# Two_Nine_Five_Rev_2.net
KiCad netlist of a schematic drawn in EAGLE
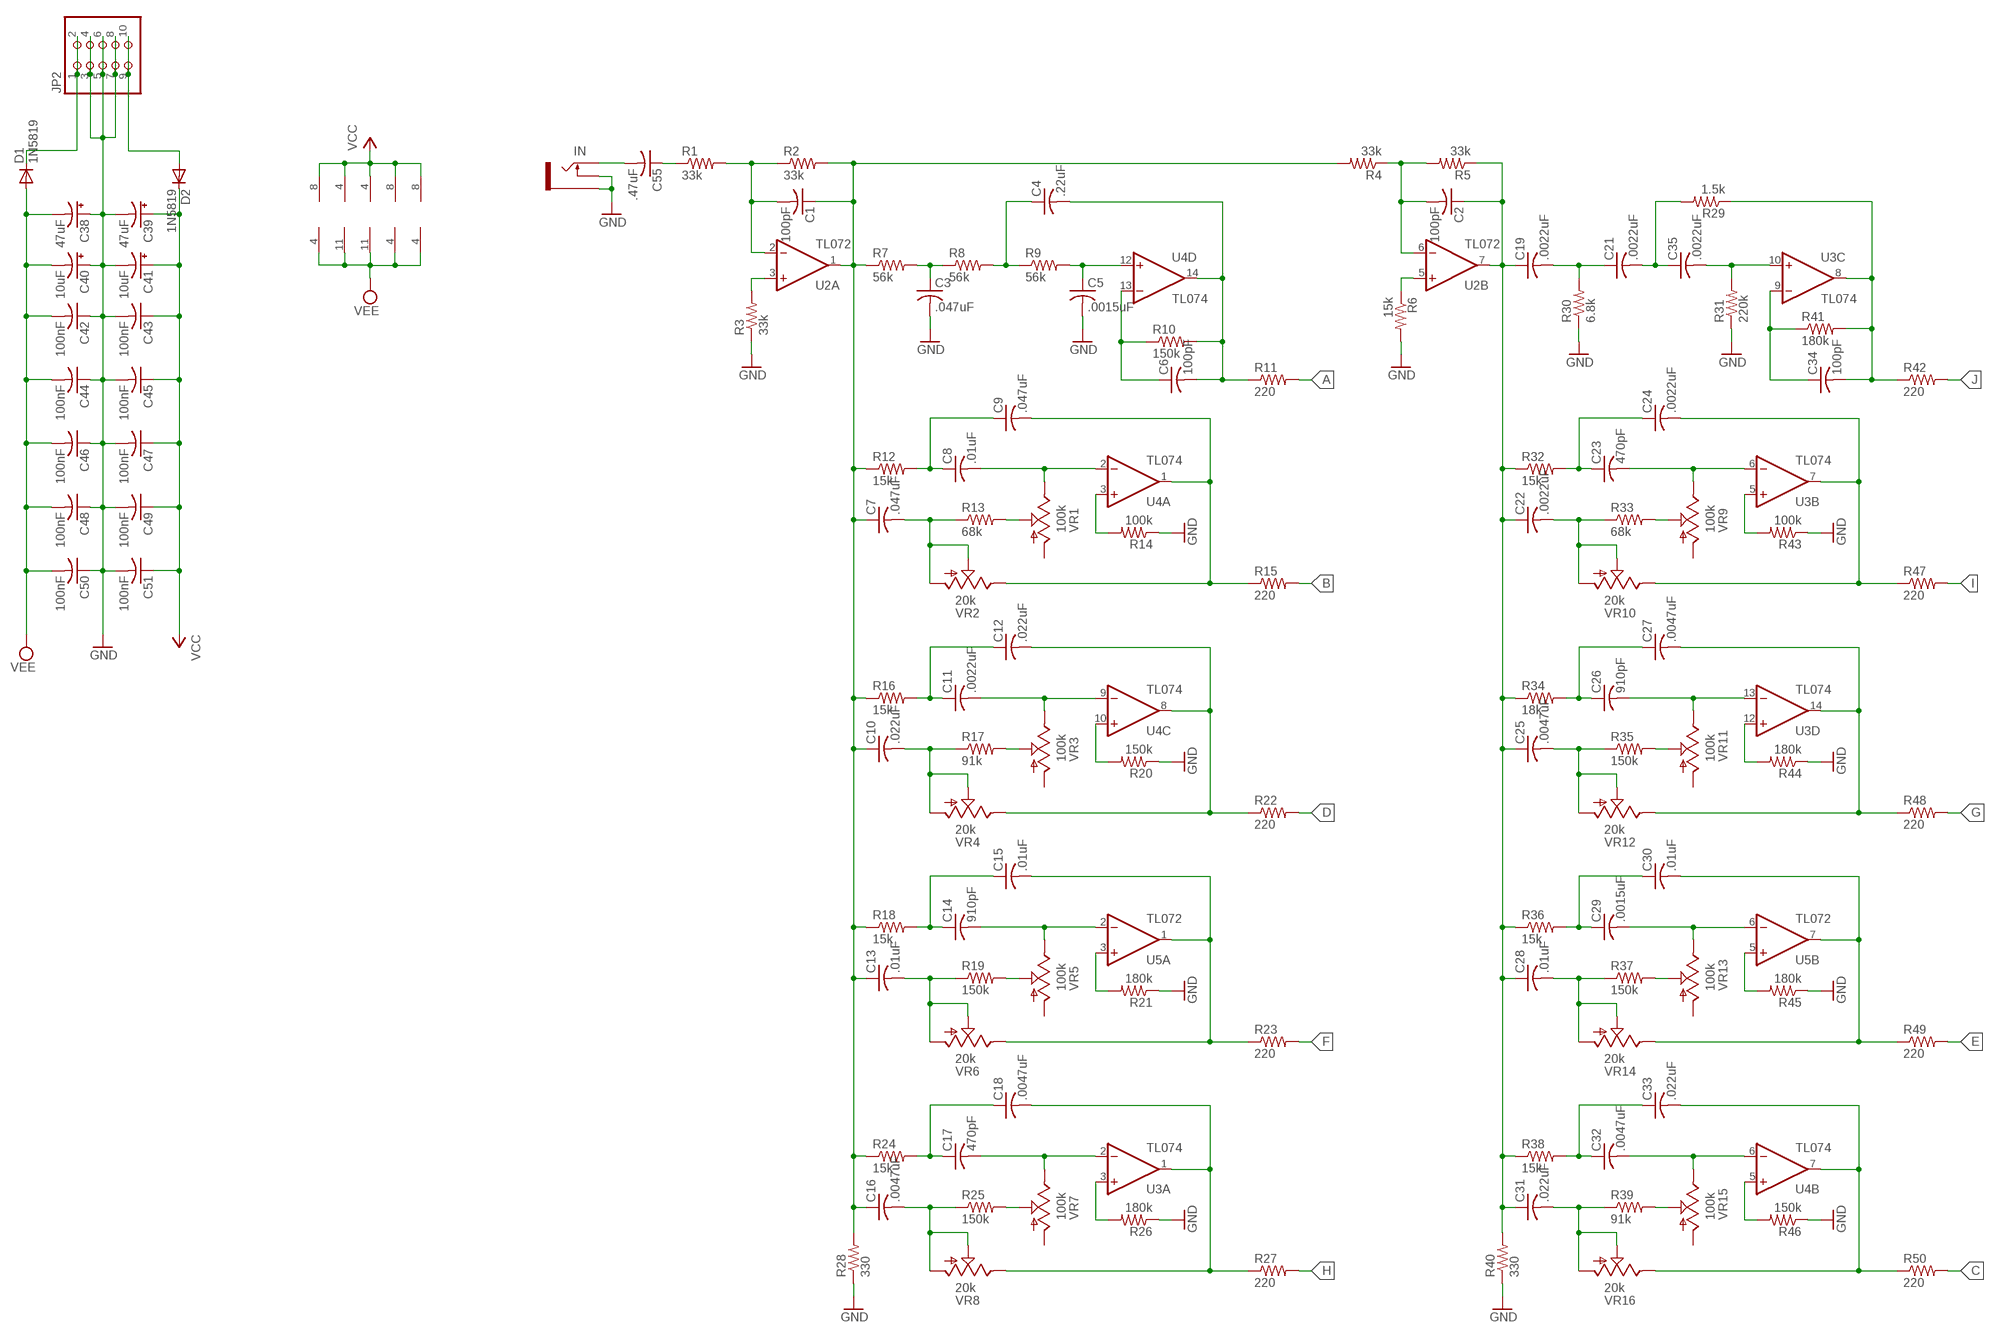
[diagram p0: schematic, sheet 1, part 1 of 2]
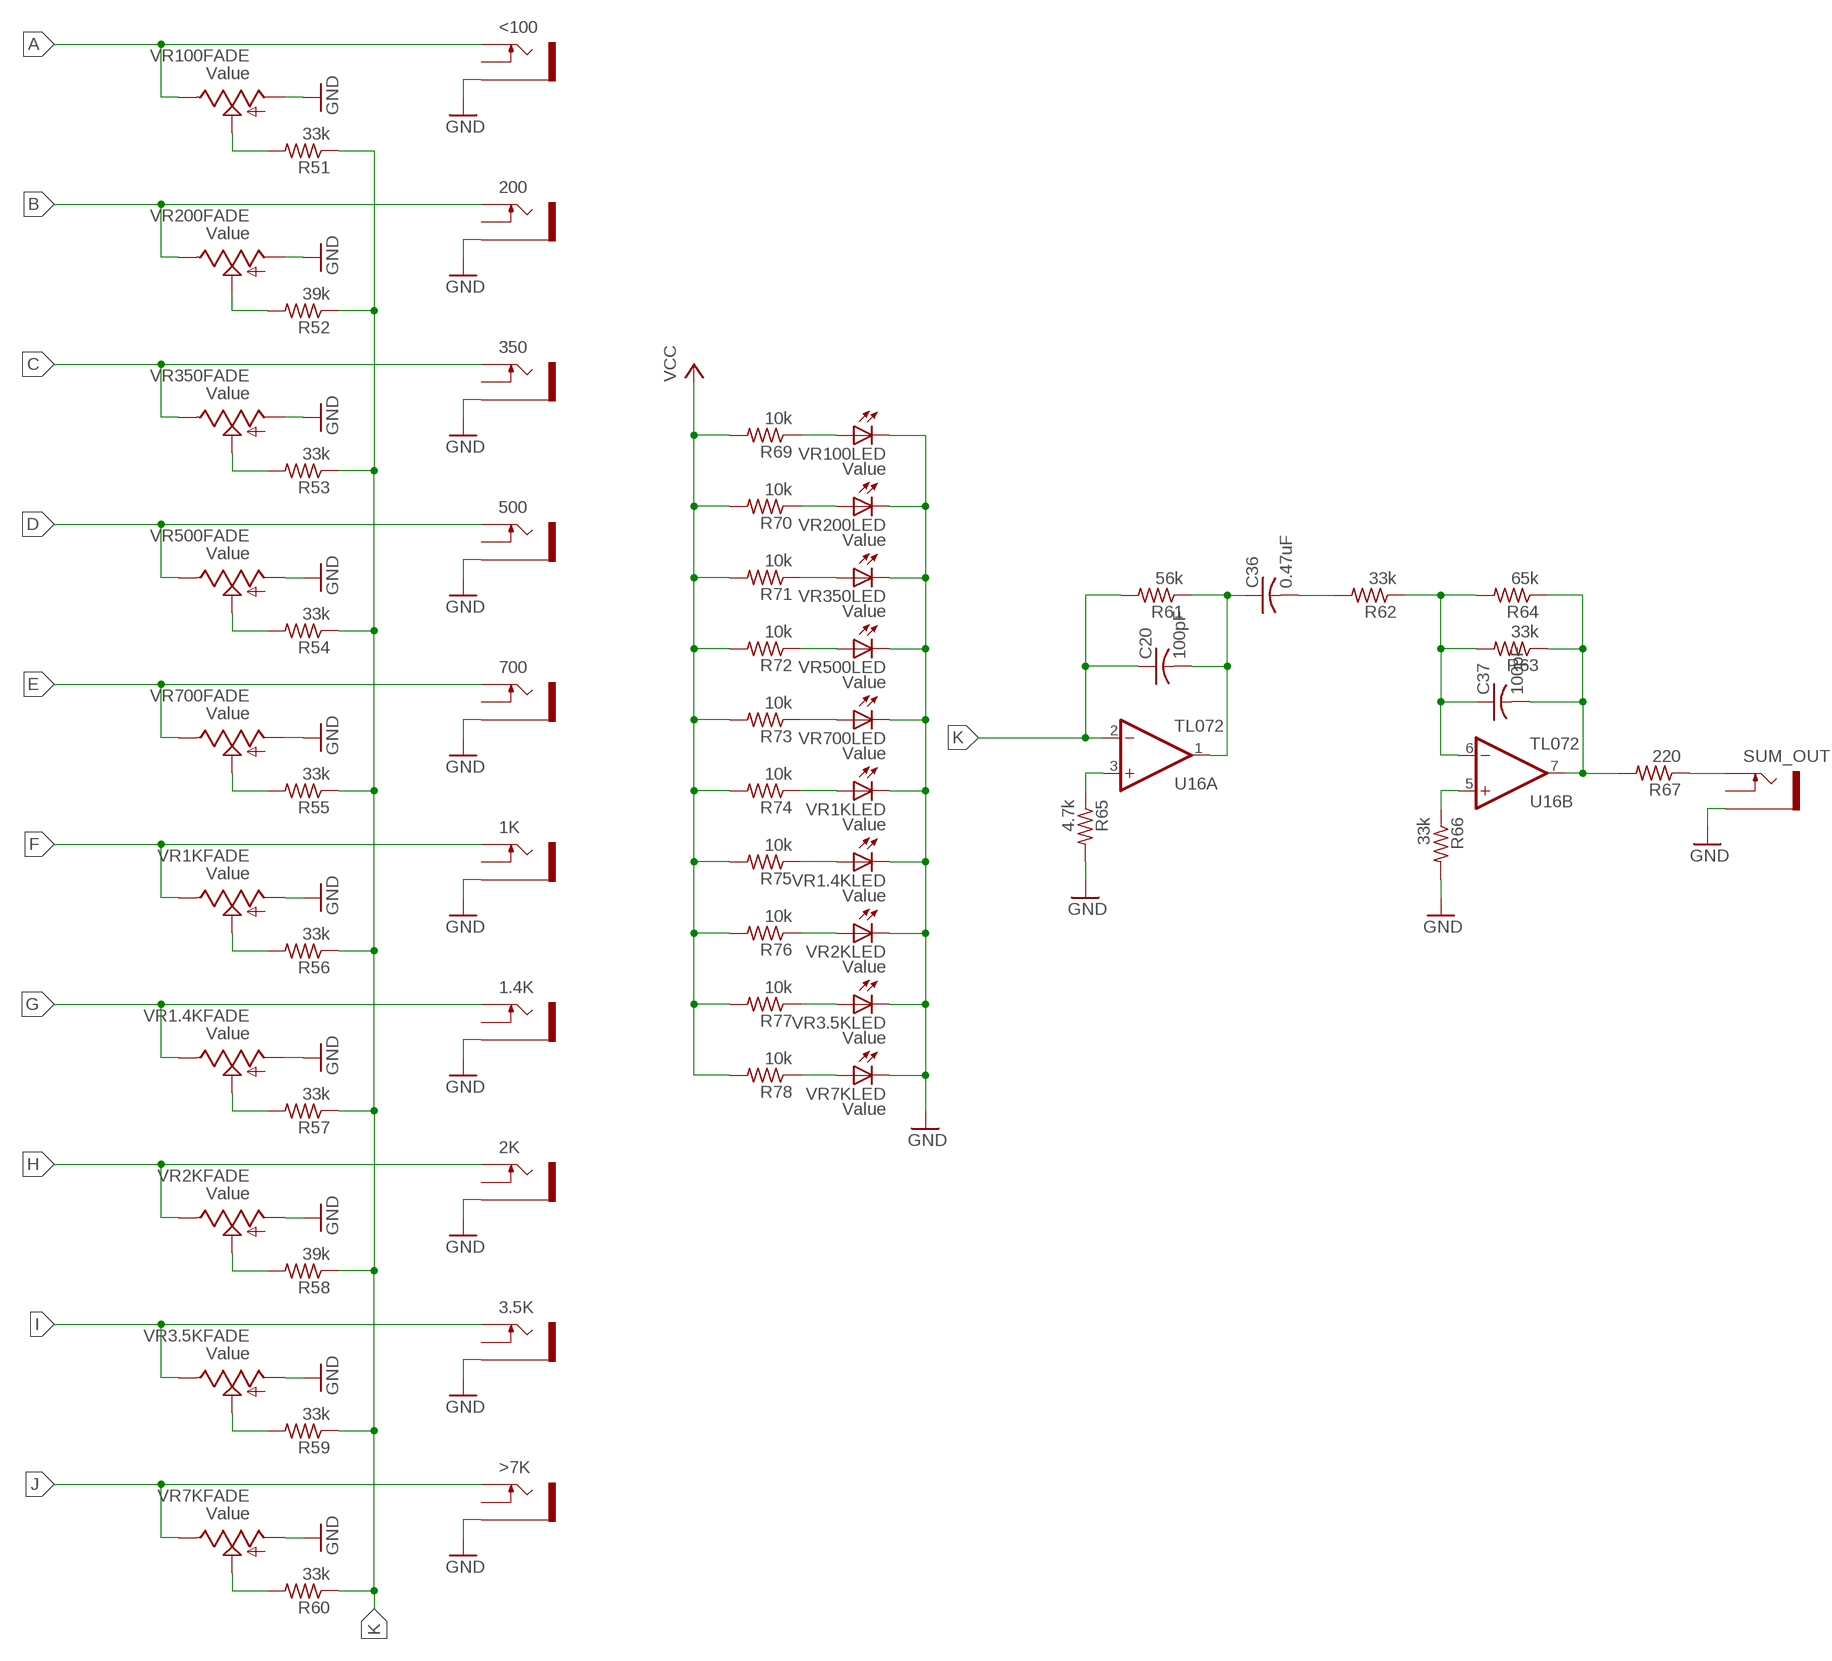
[diagram p1: schematic, sheet 1, part 2 of 2]

(export (version "E")
  (design (tool "Eeschema 10.0.6"))
  (components
    (comp (ref "1.4K")
      (value "THONKICONNNEW")
      (footprint "eagle-import:WQP-PJ301M-12_JACK")
      (libsource (lib "eagle-import") (part "THONKICONNNEW"))
    )
    (comp (ref "1K")
      (value "THONKICONNNEW")
      (footprint "eagle-import:WQP-PJ301M-12_JACK")
      (libsource (lib "eagle-import") (part "THONKICONNNEW"))
    )
    (comp (ref "2K")
      (value "THONKICONNNEW")
      (footprint "eagle-import:WQP-PJ301M-12_JACK")
      (libsource (lib "eagle-import") (part "THONKICONNNEW"))
    )
    (comp (ref "3.5K")
      (value "THONKICONNNEW")
      (footprint "eagle-import:WQP-PJ301M-12_JACK")
      (libsource (lib "eagle-import") (part "THONKICONNNEW"))
    )
    (comp (ref "200")
      (value "THONKICONNNEW")
      (footprint "eagle-import:WQP-PJ301M-12_JACK")
      (libsource (lib "eagle-import") (part "THONKICONNNEW"))
    )
    (comp (ref "350")
      (value "THONKICONNNEW")
      (footprint "eagle-import:WQP-PJ301M-12_JACK")
      (libsource (lib "eagle-import") (part "THONKICONNNEW"))
    )
    (comp (ref "500")
      (value "THONKICONNNEW")
      (footprint "eagle-import:WQP-PJ301M-12_JACK")
      (libsource (lib "eagle-import") (part "THONKICONNNEW"))
    )
    (comp (ref "700")
      (value "THONKICONNNEW")
      (footprint "eagle-import:WQP-PJ301M-12_JACK")
      (libsource (lib "eagle-import") (part "THONKICONNNEW"))
    )
    (comp (ref "<100")
      (value "THONKICONNNEW")
      (footprint "eagle-import:WQP-PJ301M-12_JACK")
      (libsource (lib "eagle-import") (part "THONKICONNNEW"))
    )
    (comp (ref ">7K")
      (value "THONKICONNNEW")
      (footprint "eagle-import:WQP-PJ301M-12_JACK")
      (libsource (lib "eagle-import") (part "THONKICONNNEW"))
    )
    (comp (ref "C1")
      (value "100pF")
      (footprint "eagle-import:C0603")
      (libsource (lib "eagle-import") (part "C-USC0603"))
    )
    (comp (ref "C2")
      (value "100pF")
      (footprint "eagle-import:C0603")
      (libsource (lib "eagle-import") (part "C-USC0603"))
    )
    (comp (ref "C3")
      (value ".047uF")
      (footprint "eagle-import:C0603")
      (libsource (lib "eagle-import") (part "C-USC0603"))
    )
    (comp (ref "C4")
      (value ".22uF")
      (footprint "eagle-import:C0603")
      (libsource (lib "eagle-import") (part "C-USC0603"))
    )
    (comp (ref "C5")
      (value ".0015uF")
      (footprint "eagle-import:C0603")
      (libsource (lib "eagle-import") (part "C-USC0603"))
    )
    (comp (ref "C6")
      (value "100pF")
      (footprint "eagle-import:C0603")
      (libsource (lib "eagle-import") (part "C-USC0603"))
    )
    (comp (ref "C7")
      (value ".047uF")
      (footprint "eagle-import:C0603")
      (libsource (lib "eagle-import") (part "C-USC0603"))
    )
    (comp (ref "C8")
      (value ".01uF")
      (footprint "eagle-import:C0603")
      (libsource (lib "eagle-import") (part "C-USC0603"))
    )
    (comp (ref "C9")
      (value ".047uF")
      (footprint "eagle-import:C0603")
      (libsource (lib "eagle-import") (part "C-USC0603"))
    )
    (comp (ref "C10")
      (value ".022uF")
      (footprint "eagle-import:C0603")
      (libsource (lib "eagle-import") (part "C-USC0603"))
    )
    (comp (ref "C11")
      (value ".0022uF")
      (footprint "eagle-import:C0603")
      (libsource (lib "eagle-import") (part "C-USC0603"))
    )
    (comp (ref "C12")
      (value ".022uF")
      (footprint "eagle-import:C0603")
      (libsource (lib "eagle-import") (part "C-USC0603"))
    )
    (comp (ref "C13")
      (value ".01uF")
      (footprint "eagle-import:C0603")
      (libsource (lib "eagle-import") (part "C-USC0603"))
    )
    (comp (ref "C14")
      (value "910pF")
      (footprint "eagle-import:C0603")
      (libsource (lib "eagle-import") (part "C-USC0603"))
    )
    (comp (ref "C15")
      (value ".01uF")
      (footprint "eagle-import:C0603")
      (libsource (lib "eagle-import") (part "C-USC0603"))
    )
    (comp (ref "C16")
      (value ".0047uF")
      (footprint "eagle-import:C0603")
      (libsource (lib "eagle-import") (part "C-USC0603"))
    )
    (comp (ref "C17")
      (value "470pF")
      (footprint "eagle-import:C0603")
      (libsource (lib "eagle-import") (part "C-USC0603"))
    )
    (comp (ref "C18")
      (value ".0047uF")
      (footprint "eagle-import:C0603")
      (libsource (lib "eagle-import") (part "C-USC0603"))
    )
    (comp (ref "C19")
      (value ".0022uF")
      (footprint "eagle-import:C0603")
      (libsource (lib "eagle-import") (part "C-USC0603"))
    )
    (comp (ref "C20")
      (value "100pF")
      (footprint "eagle-import:C0603")
      (libsource (lib "eagle-import") (part "C-USC0603"))
    )
    (comp (ref "C21")
      (value ".0022uF")
      (footprint "eagle-import:C0603")
      (libsource (lib "eagle-import") (part "C-USC0603"))
    )
    (comp (ref "C22")
      (value ".0022uF")
      (footprint "eagle-import:C0603")
      (libsource (lib "eagle-import") (part "C-USC0603"))
    )
    (comp (ref "C23")
      (value "470pF")
      (footprint "eagle-import:C0603")
      (libsource (lib "eagle-import") (part "C-USC0603"))
    )
    (comp (ref "C24")
      (value ".0022uF")
      (footprint "eagle-import:C0603")
      (libsource (lib "eagle-import") (part "C-USC0603"))
    )
    (comp (ref "C25")
      (value ".0047uF")
      (footprint "eagle-import:C0603")
      (libsource (lib "eagle-import") (part "C-USC0603"))
    )
    (comp (ref "C26")
      (value "910pF")
      (footprint "eagle-import:C0603")
      (libsource (lib "eagle-import") (part "C-USC0603"))
    )
    (comp (ref "C27")
      (value ".0047uF")
      (footprint "eagle-import:C0603")
      (libsource (lib "eagle-import") (part "C-USC0603"))
    )
    (comp (ref "C28")
      (value ".01uF")
      (footprint "eagle-import:C0603")
      (libsource (lib "eagle-import") (part "C-USC0603"))
    )
    (comp (ref "C29")
      (value ".0015uF")
      (footprint "eagle-import:C0603")
      (libsource (lib "eagle-import") (part "C-USC0603"))
    )
    (comp (ref "C30")
      (value ".01uF")
      (footprint "eagle-import:C0603")
      (libsource (lib "eagle-import") (part "C-USC0603"))
    )
    (comp (ref "C31")
      (value ".022uF")
      (footprint "eagle-import:C0603")
      (libsource (lib "eagle-import") (part "C-USC0603"))
    )
    (comp (ref "C32")
      (value ".0047uF")
      (footprint "eagle-import:C0603")
      (libsource (lib "eagle-import") (part "C-USC0603"))
    )
    (comp (ref "C33")
      (value ".022uF")
      (footprint "eagle-import:C0603")
      (libsource (lib "eagle-import") (part "C-USC0603"))
    )
    (comp (ref "C34")
      (value "100pF")
      (footprint "eagle-import:C0603")
      (libsource (lib "eagle-import") (part "C-USC0603"))
    )
    (comp (ref "C35")
      (value ".0022uF")
      (footprint "eagle-import:C0603")
      (libsource (lib "eagle-import") (part "C-USC0603"))
    )
    (comp (ref "C36")
      (value "0.47uF")
      (footprint "eagle-import:C0603")
      (libsource (lib "eagle-import") (part "C-USC0603"))
    )
    (comp (ref "C37")
      (value "100pF")
      (footprint "eagle-import:C0603")
      (libsource (lib "eagle-import") (part "C-USC0603"))
    )
    (comp (ref "C38")
      (value "47uF")
      (footprint "eagle-import:PANASONIC_D")
      (libsource (lib "eagle-import") (part "CPOL-USD"))
    )
    (comp (ref "C39")
      (value "47uF")
      (footprint "eagle-import:PANASONIC_D")
      (libsource (lib "eagle-import") (part "CPOL-USD"))
    )
    (comp (ref "C40")
      (value "10uF")
      (footprint "eagle-import:PANASONIC_B")
      (libsource (lib "eagle-import") (part "CPOL-USB"))
    )
    (comp (ref "C41")
      (value "10uF")
      (footprint "eagle-import:PANASONIC_B")
      (libsource (lib "eagle-import") (part "CPOL-USB"))
    )
    (comp (ref "C42")
      (value "100nF")
      (footprint "eagle-import:C0603")
      (libsource (lib "eagle-import") (part "C-USC0603"))
    )
    (comp (ref "C43")
      (value "100nF")
      (footprint "eagle-import:C0603")
      (libsource (lib "eagle-import") (part "C-USC0603"))
    )
    (comp (ref "C44")
      (value "100nF")
      (footprint "eagle-import:C0603")
      (libsource (lib "eagle-import") (part "C-USC0603"))
    )
    (comp (ref "C45")
      (value "100nF")
      (footprint "eagle-import:C0603")
      (libsource (lib "eagle-import") (part "C-USC0603"))
    )
    (comp (ref "C46")
      (value "100nF")
      (footprint "eagle-import:C0603")
      (libsource (lib "eagle-import") (part "C-USC0603"))
    )
    (comp (ref "C47")
      (value "100nF")
      (footprint "eagle-import:C0603")
      (libsource (lib "eagle-import") (part "C-USC0603"))
    )
    (comp (ref "C48")
      (value "100nF")
      (footprint "eagle-import:C0603")
      (libsource (lib "eagle-import") (part "C-USC0603"))
    )
    (comp (ref "C49")
      (value "100nF")
      (footprint "eagle-import:C0603")
      (libsource (lib "eagle-import") (part "C-USC0603"))
    )
    (comp (ref "C50")
      (value "100nF")
      (footprint "eagle-import:C0603")
      (libsource (lib "eagle-import") (part "C-USC0603"))
    )
    (comp (ref "C51")
      (value "100nF")
      (footprint "eagle-import:C0603")
      (libsource (lib "eagle-import") (part "C-USC0603"))
    )
    (comp (ref "C55")
      (value ".47uF")
      (footprint "eagle-import:C0603")
      (libsource (lib "eagle-import") (part "C-USC0603"))
    )
    (comp (ref "D1")
      (value "1N5819")
      (footprint "eagle-import:SOD123")
      (libsource (lib "eagle-import") (part "DIODE-SOD123"))
    )
    (comp (ref "D2")
      (value "1N5819")
      (footprint "eagle-import:SOD123")
      (libsource (lib "eagle-import") (part "DIODE-SOD123"))
    )
    (comp (ref "IN")
      (value "THONKICONNNEW")
      (footprint "eagle-import:WQP-PJ301M-12_JACK")
      (libsource (lib "eagle-import") (part "THONKICONNNEW"))
    )
    (comp (ref "JP2")
      (value "PINHD-2X5SMT")
      (footprint "eagle-import:2X05_SMT")
      (libsource (lib "eagle-import") (part "PINHD-2X5SMT"))
    )
    (comp (ref "R1")
      (value "33k")
      (footprint "eagle-import:R0603")
      (libsource (lib "eagle-import") (part "R-US_R0603"))
    )
    (comp (ref "R2")
      (value "33k")
      (footprint "eagle-import:R0603")
      (libsource (lib "eagle-import") (part "R-US_R0603"))
    )
    (comp (ref "R3")
      (value "33k")
      (footprint "eagle-import:R0603")
      (libsource (lib "eagle-import") (part "R-US_R0603"))
    )
    (comp (ref "R4")
      (value "33k")
      (footprint "eagle-import:R0603")
      (libsource (lib "eagle-import") (part "R-US_R0603"))
    )
    (comp (ref "R5")
      (value "33k")
      (footprint "eagle-import:R0603")
      (libsource (lib "eagle-import") (part "R-US_R0603"))
    )
    (comp (ref "R6")
      (value "15k")
      (footprint "eagle-import:R0603")
      (libsource (lib "eagle-import") (part "R-US_R0603"))
    )
    (comp (ref "R7")
      (value "56k")
      (footprint "eagle-import:R0603")
      (libsource (lib "eagle-import") (part "R-US_R0603"))
    )
    (comp (ref "R8")
      (value "56k")
      (footprint "eagle-import:R0603")
      (libsource (lib "eagle-import") (part "R-US_R0603"))
    )
    (comp (ref "R9")
      (value "56k")
      (footprint "eagle-import:R0603")
      (libsource (lib "eagle-import") (part "R-US_R0603"))
    )
    (comp (ref "R10")
      (value "150k")
      (footprint "eagle-import:R0603")
      (libsource (lib "eagle-import") (part "R-US_R0603"))
    )
    (comp (ref "R11")
      (value "220")
      (footprint "eagle-import:R0603")
      (libsource (lib "eagle-import") (part "R-US_R0603"))
    )
    (comp (ref "R12")
      (value "15k")
      (footprint "eagle-import:R0603")
      (libsource (lib "eagle-import") (part "R-US_R0603"))
    )
    (comp (ref "R13")
      (value "68k")
      (footprint "eagle-import:R0603")
      (libsource (lib "eagle-import") (part "R-US_R0603"))
    )
    (comp (ref "R14")
      (value "100k")
      (footprint "eagle-import:R0603")
      (libsource (lib "eagle-import") (part "R-US_R0603"))
    )
    (comp (ref "R15")
      (value "220")
      (footprint "eagle-import:R0603")
      (libsource (lib "eagle-import") (part "R-US_R0603"))
    )
    (comp (ref "R16")
      (value "15k")
      (footprint "eagle-import:R0603")
      (libsource (lib "eagle-import") (part "R-US_R0603"))
    )
    (comp (ref "R17")
      (value "91k")
      (footprint "eagle-import:R0603")
      (libsource (lib "eagle-import") (part "R-US_R0603"))
    )
    (comp (ref "R18")
      (value "15k")
      (footprint "eagle-import:R0603")
      (libsource (lib "eagle-import") (part "R-US_R0603"))
    )
    (comp (ref "R19")
      (value "150k")
      (footprint "eagle-import:R0603")
      (libsource (lib "eagle-import") (part "R-US_R0603"))
    )
    (comp (ref "R20")
      (value "150k")
      (footprint "eagle-import:R0603")
      (libsource (lib "eagle-import") (part "R-US_R0603"))
    )
    (comp (ref "R21")
      (value "180k")
      (footprint "eagle-import:R0603")
      (libsource (lib "eagle-import") (part "R-US_R0603"))
    )
    (comp (ref "R22")
      (value "220")
      (footprint "eagle-import:R0603")
      (libsource (lib "eagle-import") (part "R-US_R0603"))
    )
    (comp (ref "R23")
      (value "220")
      (footprint "eagle-import:R0603")
      (libsource (lib "eagle-import") (part "R-US_R0603"))
    )
    (comp (ref "R24")
      (value "15k")
      (footprint "eagle-import:R0603")
      (libsource (lib "eagle-import") (part "R-US_R0603"))
    )
    (comp (ref "R25")
      (value "150k")
      (footprint "eagle-import:R0603")
      (libsource (lib "eagle-import") (part "R-US_R0603"))
    )
    (comp (ref "R26")
      (value "180k")
      (footprint "eagle-import:R0603")
      (libsource (lib "eagle-import") (part "R-US_R0603"))
    )
    (comp (ref "R27")
      (value "220")
      (footprint "eagle-import:R0603")
      (libsource (lib "eagle-import") (part "R-US_R0603"))
    )
    (comp (ref "R28")
      (value "330")
      (footprint "eagle-import:R0603")
      (libsource (lib "eagle-import") (part "R-US_R0603"))
    )
    (comp (ref "R29")
      (value "1.5k")
      (footprint "eagle-import:R0603")
      (libsource (lib "eagle-import") (part "R-US_R0603"))
    )
    (comp (ref "R30")
      (value "6.8k")
      (footprint "eagle-import:R0603")
      (libsource (lib "eagle-import") (part "R-US_R0603"))
    )
    (comp (ref "R31")
      (value "220k")
      (footprint "eagle-import:R0603")
      (libsource (lib "eagle-import") (part "R-US_R0603"))
    )
    (comp (ref "R32")
      (value "15k")
      (footprint "eagle-import:R0603")
      (libsource (lib "eagle-import") (part "R-US_R0603"))
    )
    (comp (ref "R33")
      (value "68k")
      (footprint "eagle-import:R0603")
      (libsource (lib "eagle-import") (part "R-US_R0603"))
    )
    (comp (ref "R34")
      (value "18k")
      (footprint "eagle-import:R0603")
      (libsource (lib "eagle-import") (part "R-US_R0603"))
    )
    (comp (ref "R35")
      (value "150k")
      (footprint "eagle-import:R0603")
      (libsource (lib "eagle-import") (part "R-US_R0603"))
    )
    (comp (ref "R36")
      (value "15k")
      (footprint "eagle-import:R0603")
      (libsource (lib "eagle-import") (part "R-US_R0603"))
    )
    (comp (ref "R37")
      (value "150k")
      (footprint "eagle-import:R0603")
      (libsource (lib "eagle-import") (part "R-US_R0603"))
    )
    (comp (ref "R38")
      (value "15k")
      (footprint "eagle-import:R0603")
      (libsource (lib "eagle-import") (part "R-US_R0603"))
    )
    (comp (ref "R39")
      (value "91k")
      (footprint "eagle-import:R0603")
      (libsource (lib "eagle-import") (part "R-US_R0603"))
    )
    (comp (ref "R40")
      (value "330")
      (footprint "eagle-import:R0603")
      (libsource (lib "eagle-import") (part "R-US_R0603"))
    )
    (comp (ref "R41")
      (value "180k")
      (footprint "eagle-import:R0603")
      (libsource (lib "eagle-import") (part "R-US_R0603"))
    )
    (comp (ref "R42")
      (value "220")
      (footprint "eagle-import:R0603")
      (libsource (lib "eagle-import") (part "R-US_R0603"))
    )
    (comp (ref "R43")
      (value "100k")
      (footprint "eagle-import:R0603")
      (libsource (lib "eagle-import") (part "R-US_R0603"))
    )
    (comp (ref "R44")
      (value "180k")
      (footprint "eagle-import:R0603")
      (libsource (lib "eagle-import") (part "R-US_R0603"))
    )
    (comp (ref "R45")
      (value "180k")
      (footprint "eagle-import:R0603")
      (libsource (lib "eagle-import") (part "R-US_R0603"))
    )
    (comp (ref "R46")
      (value "150k")
      (footprint "eagle-import:R0603")
      (libsource (lib "eagle-import") (part "R-US_R0603"))
    )
    (comp (ref "R47")
      (value "220")
      (footprint "eagle-import:R0603")
      (libsource (lib "eagle-import") (part "R-US_R0603"))
    )
    (comp (ref "R48")
      (value "220")
      (footprint "eagle-import:R0603")
      (libsource (lib "eagle-import") (part "R-US_R0603"))
    )
    (comp (ref "R49")
      (value "220")
      (footprint "eagle-import:R0603")
      (libsource (lib "eagle-import") (part "R-US_R0603"))
    )
    (comp (ref "R50")
      (value "220")
      (footprint "eagle-import:R0603")
      (libsource (lib "eagle-import") (part "R-US_R0603"))
    )
    (comp (ref "R51")
      (value "33k")
      (footprint "eagle-import:R0603")
      (libsource (lib "eagle-import") (part "R-US_R0603"))
    )
    (comp (ref "R52")
      (value "39k")
      (footprint "eagle-import:R0603")
      (libsource (lib "eagle-import") (part "R-US_R0603"))
    )
    (comp (ref "R53")
      (value "33k")
      (footprint "eagle-import:R0603")
      (libsource (lib "eagle-import") (part "R-US_R0603"))
    )
    (comp (ref "R54")
      (value "33k")
      (footprint "eagle-import:R0603")
      (libsource (lib "eagle-import") (part "R-US_R0603"))
    )
    (comp (ref "R55")
      (value "33k")
      (footprint "eagle-import:R0603")
      (libsource (lib "eagle-import") (part "R-US_R0603"))
    )
    (comp (ref "R56")
      (value "33k")
      (footprint "eagle-import:R0603")
      (libsource (lib "eagle-import") (part "R-US_R0603"))
    )
    (comp (ref "R57")
      (value "33k")
      (footprint "eagle-import:R0603")
      (libsource (lib "eagle-import") (part "R-US_R0603"))
    )
    (comp (ref "R58")
      (value "39k")
      (footprint "eagle-import:R0603")
      (libsource (lib "eagle-import") (part "R-US_R0603"))
    )
    (comp (ref "R59")
      (value "33k")
      (footprint "eagle-import:R0603")
      (libsource (lib "eagle-import") (part "R-US_R0603"))
    )
    (comp (ref "R60")
      (value "33k")
      (footprint "eagle-import:R0603")
      (libsource (lib "eagle-import") (part "R-US_R0603"))
    )
    (comp (ref "R61")
      (value "56k")
      (footprint "eagle-import:R0603")
      (libsource (lib "eagle-import") (part "R-US_R0603"))
    )
    (comp (ref "R62")
      (value "33k")
      (footprint "eagle-import:R0603")
      (libsource (lib "eagle-import") (part "R-US_R0603"))
    )
    (comp (ref "R63")
      (value "33k")
      (footprint "eagle-import:R0603")
      (libsource (lib "eagle-import") (part "R-US_R0603"))
    )
    (comp (ref "R64")
      (value "65k")
      (footprint "eagle-import:R0603")
      (libsource (lib "eagle-import") (part "R-US_R0603"))
    )
    (comp (ref "R65")
      (value "4.7k")
      (footprint "eagle-import:R0603")
      (libsource (lib "eagle-import") (part "R-US_R0603"))
    )
    (comp (ref "R66")
      (value "33k")
      (footprint "eagle-import:R0603")
      (libsource (lib "eagle-import") (part "R-US_R0603"))
    )
    (comp (ref "R67")
      (value "220")
      (footprint "eagle-import:R0603")
      (libsource (lib "eagle-import") (part "R-US_R0603"))
    )
    (comp (ref "R69")
      (value "10k")
      (footprint "eagle-import:R0603")
      (libsource (lib "eagle-import") (part "R-US_R0603"))
    )
    (comp (ref "R70")
      (value "10k")
      (footprint "eagle-import:R0603")
      (libsource (lib "eagle-import") (part "R-US_R0603"))
    )
    (comp (ref "R71")
      (value "10k")
      (footprint "eagle-import:R0603")
      (libsource (lib "eagle-import") (part "R-US_R0603"))
    )
    (comp (ref "R72")
      (value "10k")
      (footprint "eagle-import:R0603")
      (libsource (lib "eagle-import") (part "R-US_R0603"))
    )
    (comp (ref "R73")
      (value "10k")
      (footprint "eagle-import:R0603")
      (libsource (lib "eagle-import") (part "R-US_R0603"))
    )
    (comp (ref "R74")
      (value "10k")
      (footprint "eagle-import:R0603")
      (libsource (lib "eagle-import") (part "R-US_R0603"))
    )
    (comp (ref "R75")
      (value "10k")
      (footprint "eagle-import:R0603")
      (libsource (lib "eagle-import") (part "R-US_R0603"))
    )
    (comp (ref "R76")
      (value "10k")
      (footprint "eagle-import:R0603")
      (libsource (lib "eagle-import") (part "R-US_R0603"))
    )
    (comp (ref "R77")
      (value "10k")
      (footprint "eagle-import:R0603")
      (libsource (lib "eagle-import") (part "R-US_R0603"))
    )
    (comp (ref "R78")
      (value "10k")
      (footprint "eagle-import:R0603")
      (libsource (lib "eagle-import") (part "R-US_R0603"))
    )
    (comp (ref "SUM_OUT")
      (value "THONKICONNNEW")
      (footprint "eagle-import:WQP-PJ301M-12_JACK")
      (libsource (lib "eagle-import") (part "THONKICONNNEW"))
    )
    (comp (ref "U2")
      (value "TL072")
      (footprint "eagle-import:SO08")
      (libsource (lib "eagle-import") (part "TL072_SMD"))
    )
    (comp (ref "U3")
      (value "TL074")
      (footprint "eagle-import:SO14")
      (libsource (lib "eagle-import") (part "TL074_SMD"))
    )
    (comp (ref "U4")
      (value "TL074")
      (footprint "eagle-import:SO14")
      (libsource (lib "eagle-import") (part "TL074_SMD"))
    )
    (comp (ref "U5")
      (value "TL072")
      (footprint "eagle-import:SO08")
      (libsource (lib "eagle-import") (part "TL072_SMD"))
    )
    (comp (ref "U16")
      (value "TL072")
      (footprint "eagle-import:SO08")
      (libsource (lib "eagle-import") (part "TL072_SMD"))
    )
    (comp (ref "VR1")
      (value "100k")
      (footprint "eagle-import:RJ9W")
      (libsource (lib "eagle-import") (part "TRIM_US-RJ9W"))
    )
    (comp (ref "VR1.4K")
      (value "Value")
      (footprint "eagle-import:ALPHA_ILL_FADER_20MM_REV2")
      (libsource (lib "eagle-import") (part "ALPHA_20MM_ILLUM_FADER"))
    )
    (comp (ref "VR1K")
      (value "Value")
      (footprint "eagle-import:ALPHA_ILL_FADER_20MM_REV2")
      (libsource (lib "eagle-import") (part "ALPHA_20MM_ILLUM_FADER"))
    )
    (comp (ref "VR2")
      (value "20k")
      (footprint "eagle-import:RJ9W")
      (libsource (lib "eagle-import") (part "TRIM_US-RJ9W"))
    )
    (comp (ref "VR2K")
      (value "Value")
      (footprint "eagle-import:ALPHA_ILL_FADER_20MM_REV2")
      (libsource (lib "eagle-import") (part "ALPHA_20MM_ILLUM_FADER"))
    )
    (comp (ref "VR3")
      (value "100k")
      (footprint "eagle-import:RJ9W")
      (libsource (lib "eagle-import") (part "TRIM_US-RJ9W"))
    )
    (comp (ref "VR3.5K")
      (value "Value")
      (footprint "eagle-import:ALPHA_ILL_FADER_20MM_REV2")
      (libsource (lib "eagle-import") (part "ALPHA_20MM_ILLUM_FADER"))
    )
    (comp (ref "VR4")
      (value "20k")
      (footprint "eagle-import:RJ9W")
      (libsource (lib "eagle-import") (part "TRIM_US-RJ9W"))
    )
    (comp (ref "VR5")
      (value "100k")
      (footprint "eagle-import:RJ9W")
      (libsource (lib "eagle-import") (part "TRIM_US-RJ9W"))
    )
    (comp (ref "VR6")
      (value "20k")
      (footprint "eagle-import:RJ9W")
      (libsource (lib "eagle-import") (part "TRIM_US-RJ9W"))
    )
    (comp (ref "VR7")
      (value "100k")
      (footprint "eagle-import:RJ9W")
      (libsource (lib "eagle-import") (part "TRIM_US-RJ9W"))
    )
    (comp (ref "VR7K")
      (value "Value")
      (footprint "eagle-import:ALPHA_ILL_FADER_20MM_REV2")
      (libsource (lib "eagle-import") (part "ALPHA_20MM_ILLUM_FADER"))
    )
    (comp (ref "VR8")
      (value "20k")
      (footprint "eagle-import:RJ9W")
      (libsource (lib "eagle-import") (part "TRIM_US-RJ9W"))
    )
    (comp (ref "VR9")
      (value "100k")
      (footprint "eagle-import:RJ9W")
      (libsource (lib "eagle-import") (part "TRIM_US-RJ9W"))
    )
    (comp (ref "VR10")
      (value "20k")
      (footprint "eagle-import:RJ9W")
      (libsource (lib "eagle-import") (part "TRIM_US-RJ9W"))
    )
    (comp (ref "VR11")
      (value "100k")
      (footprint "eagle-import:RJ9W")
      (libsource (lib "eagle-import") (part "TRIM_US-RJ9W"))
    )
    (comp (ref "VR12")
      (value "20k")
      (footprint "eagle-import:RJ9W")
      (libsource (lib "eagle-import") (part "TRIM_US-RJ9W"))
    )
    (comp (ref "VR13")
      (value "100k")
      (footprint "eagle-import:RJ9W")
      (libsource (lib "eagle-import") (part "TRIM_US-RJ9W"))
    )
    (comp (ref "VR14")
      (value "20k")
      (footprint "eagle-import:RJ9W")
      (libsource (lib "eagle-import") (part "TRIM_US-RJ9W"))
    )
    (comp (ref "VR15")
      (value "100k")
      (footprint "eagle-import:RJ9W")
      (libsource (lib "eagle-import") (part "TRIM_US-RJ9W"))
    )
    (comp (ref "VR16")
      (value "20k")
      (footprint "eagle-import:RJ9W")
      (libsource (lib "eagle-import") (part "TRIM_US-RJ9W"))
    )
    (comp (ref "VR100")
      (value "Value")
      (footprint "eagle-import:ALPHA_ILL_FADER_20MM_REV2")
      (libsource (lib "eagle-import") (part "ALPHA_20MM_ILLUM_FADER"))
    )
    (comp (ref "VR200")
      (value "Value")
      (footprint "eagle-import:ALPHA_ILL_FADER_20MM_REV2")
      (libsource (lib "eagle-import") (part "ALPHA_20MM_ILLUM_FADER"))
    )
    (comp (ref "VR350")
      (value "Value")
      (footprint "eagle-import:ALPHA_ILL_FADER_20MM_REV2")
      (libsource (lib "eagle-import") (part "ALPHA_20MM_ILLUM_FADER"))
    )
    (comp (ref "VR500")
      (value "Value")
      (footprint "eagle-import:ALPHA_ILL_FADER_20MM_REV2")
      (libsource (lib "eagle-import") (part "ALPHA_20MM_ILLUM_FADER"))
    )
    (comp (ref "VR700")
      (value "Value")
      (footprint "eagle-import:ALPHA_ILL_FADER_20MM_REV2")
      (libsource (lib "eagle-import") (part "ALPHA_20MM_ILLUM_FADER"))
    )
  )
  (nets
    (net (code "1") (name "A") (class "Default")
      (node (ref "<100") (pin "P$1_TIP") (pinfunction "TIP_P$1_TIP") (pintype "passive"))
      (node (ref "R11") (pin "2") (pinfunction "2_2") (pintype "passive"))
      (node (ref "VR100") (pin "1") (pinfunction "E_1") (pintype "passive"))
    )
    (net (code "2") (name "B") (class "Default")
      (node (ref "200") (pin "P$1_TIP") (pinfunction "TIP_P$1_TIP") (pintype "passive"))
      (node (ref "R15") (pin "2") (pinfunction "2_2") (pintype "passive"))
      (node (ref "VR200") (pin "1") (pinfunction "E_1") (pintype "passive"))
    )
    (net (code "3") (name "C") (class "Default")
      (node (ref "350") (pin "P$1_TIP") (pinfunction "TIP_P$1_TIP") (pintype "passive"))
      (node (ref "R50") (pin "2") (pinfunction "2_2") (pintype "passive"))
      (node (ref "VR350") (pin "1") (pinfunction "E_1") (pintype "passive"))
    )
    (net (code "4") (name "D") (class "Default")
      (node (ref "500") (pin "P$1_TIP") (pinfunction "TIP_P$1_TIP") (pintype "passive"))
      (node (ref "R22") (pin "2") (pinfunction "2_2") (pintype "passive"))
      (node (ref "VR500") (pin "1") (pinfunction "E_1") (pintype "passive"))
    )
    (net (code "5") (name "E") (class "Default")
      (node (ref "700") (pin "P$1_TIP") (pinfunction "TIP_P$1_TIP") (pintype "passive"))
      (node (ref "R49") (pin "2") (pinfunction "2_2") (pintype "passive"))
      (node (ref "VR700") (pin "1") (pinfunction "E_1") (pintype "passive"))
    )
    (net (code "6") (name "F") (class "Default")
      (node (ref "1K") (pin "P$1_TIP") (pinfunction "TIP_P$1_TIP") (pintype "passive"))
      (node (ref "R23") (pin "2") (pinfunction "2_2") (pintype "passive"))
      (node (ref "VR1K") (pin "1") (pinfunction "E_1") (pintype "passive"))
    )
    (net (code "7") (name "G") (class "Default")
      (node (ref "1.4K") (pin "P$1_TIP") (pinfunction "TIP_P$1_TIP") (pintype "passive"))
      (node (ref "R48") (pin "2") (pinfunction "2_2") (pintype "passive"))
      (node (ref "VR1.4K") (pin "1") (pinfunction "E_1") (pintype "passive"))
    )
    (net (code "8") (name "GND") (class "Default")
      (node (ref "1.4K") (pin "P$3_SLEEVE") (pinfunction "SLEEVE_P$3_SLEEVE") (pintype "passive"))
      (node (ref "1K") (pin "P$3_SLEEVE") (pinfunction "SLEEVE_P$3_SLEEVE") (pintype "passive"))
      (node (ref "200") (pin "P$3_SLEEVE") (pinfunction "SLEEVE_P$3_SLEEVE") (pintype "passive"))
      (node (ref "2K") (pin "P$3_SLEEVE") (pinfunction "SLEEVE_P$3_SLEEVE") (pintype "passive"))
      (node (ref "3.5K") (pin "P$3_SLEEVE") (pinfunction "SLEEVE_P$3_SLEEVE") (pintype "passive"))
      (node (ref "350") (pin "P$3_SLEEVE") (pinfunction "SLEEVE_P$3_SLEEVE") (pintype "passive"))
      (node (ref "500") (pin "P$3_SLEEVE") (pinfunction "SLEEVE_P$3_SLEEVE") (pintype "passive"))
      (node (ref "700") (pin "P$3_SLEEVE") (pinfunction "SLEEVE_P$3_SLEEVE") (pintype "passive"))
      (node (ref "<100") (pin "P$3_SLEEVE") (pinfunction "SLEEVE_P$3_SLEEVE") (pintype "passive"))
      (node (ref ">7K") (pin "P$3_SLEEVE") (pinfunction "SLEEVE_P$3_SLEEVE") (pintype "passive"))
      (node (ref "C3") (pin "2") (pinfunction "2_2") (pintype "passive"))
      (node (ref "C38") (pin "+") (pinfunction "+_+") (pintype "passive"))
      (node (ref "C39") (pin "-") (pinfunction "-_-") (pintype "passive"))
      (node (ref "C40") (pin "+") (pinfunction "+_+") (pintype "passive"))
      (node (ref "C41") (pin "-") (pinfunction "-_-") (pintype "passive"))
      (node (ref "C42") (pin "1") (pinfunction "1_1") (pintype "passive"))
      (node (ref "C43") (pin "2") (pinfunction "2_2") (pintype "passive"))
      (node (ref "C44") (pin "1") (pinfunction "1_1") (pintype "passive"))
      (node (ref "C45") (pin "2") (pinfunction "2_2") (pintype "passive"))
      (node (ref "C46") (pin "1") (pinfunction "1_1") (pintype "passive"))
      (node (ref "C47") (pin "2") (pinfunction "2_2") (pintype "passive"))
      (node (ref "C48") (pin "1") (pinfunction "1_1") (pintype "passive"))
      (node (ref "C49") (pin "2") (pinfunction "2_2") (pintype "passive"))
      (node (ref "C5") (pin "2") (pinfunction "2_2") (pintype "passive"))
      (node (ref "C50") (pin "1") (pinfunction "1_1") (pintype "passive"))
      (node (ref "C51") (pin "2") (pinfunction "2_2") (pintype "passive"))
      (node (ref "IN") (pin "P$2_SWITCH") (pinfunction "SWITCH_P$2_SWITCH") (pintype "passive"))
      (node (ref "IN") (pin "P$3_SLEEVE") (pinfunction "SLEEVE_P$3_SLEEVE") (pintype "passive"))
      (node (ref "JP2") (pin "3") (pinfunction "3_3") (pintype "passive"))
      (node (ref "JP2") (pin "4") (pinfunction "4_4") (pintype "passive"))
      (node (ref "JP2") (pin "5") (pinfunction "5_5") (pintype "passive"))
      (node (ref "JP2") (pin "6") (pinfunction "6_6") (pintype "passive"))
      (node (ref "JP2") (pin "7") (pinfunction "7_7") (pintype "passive"))
      (node (ref "JP2") (pin "8") (pinfunction "8_8") (pintype "passive"))
      (node (ref "R14") (pin "1") (pinfunction "1_1") (pintype "passive"))
      (node (ref "R20") (pin "1") (pinfunction "1_1") (pintype "passive"))
      (node (ref "R21") (pin "1") (pinfunction "1_1") (pintype "passive"))
      (node (ref "R26") (pin "1") (pinfunction "1_1") (pintype "passive"))
      (node (ref "R28") (pin "1") (pinfunction "1_1") (pintype "passive"))
      (node (ref "R3") (pin "1") (pinfunction "1_1") (pintype "passive"))
      (node (ref "R30") (pin "1") (pinfunction "1_1") (pintype "passive"))
      (node (ref "R31") (pin "1") (pinfunction "1_1") (pintype "passive"))
      (node (ref "R40") (pin "1") (pinfunction "1_1") (pintype "passive"))
      (node (ref "R43") (pin "1") (pinfunction "1_1") (pintype "passive"))
      (node (ref "R44") (pin "1") (pinfunction "1_1") (pintype "passive"))
      (node (ref "R45") (pin "1") (pinfunction "1_1") (pintype "passive"))
      (node (ref "R46") (pin "1") (pinfunction "1_1") (pintype "passive"))
      (node (ref "R6") (pin "2") (pinfunction "2_2") (pintype "passive"))
      (node (ref "R65") (pin "2") (pinfunction "2_2") (pintype "passive"))
      (node (ref "R66") (pin "2") (pinfunction "2_2") (pintype "passive"))
      (node (ref "SUM_OUT") (pin "P$3_SLEEVE") (pinfunction "SLEEVE_P$3_SLEEVE") (pintype "passive"))
      (node (ref "VR1.4K") (pin "3") (pinfunction "A_3") (pintype "passive"))
      (node (ref "VR1.4K") (pin "E") (pinfunction "C_E") (pintype "passive"))
      (node (ref "VR100") (pin "3") (pinfunction "A_3") (pintype "passive"))
      (node (ref "VR100") (pin "E") (pinfunction "C_E") (pintype "passive"))
      (node (ref "VR1K") (pin "3") (pinfunction "A_3") (pintype "passive"))
      (node (ref "VR1K") (pin "E") (pinfunction "C_E") (pintype "passive"))
      (node (ref "VR200") (pin "3") (pinfunction "A_3") (pintype "passive"))
      (node (ref "VR200") (pin "E") (pinfunction "C_E") (pintype "passive"))
      (node (ref "VR2K") (pin "3") (pinfunction "A_3") (pintype "passive"))
      (node (ref "VR2K") (pin "E") (pinfunction "C_E") (pintype "passive"))
      (node (ref "VR3.5K") (pin "3") (pinfunction "A_3") (pintype "passive"))
      (node (ref "VR3.5K") (pin "E") (pinfunction "C_E") (pintype "passive"))
      (node (ref "VR350") (pin "3") (pinfunction "A_3") (pintype "passive"))
      (node (ref "VR350") (pin "E") (pinfunction "C_E") (pintype "passive"))
      (node (ref "VR500") (pin "3") (pinfunction "A_3") (pintype "passive"))
      (node (ref "VR500") (pin "E") (pinfunction "C_E") (pintype "passive"))
      (node (ref "VR700") (pin "3") (pinfunction "A_3") (pintype "passive"))
      (node (ref "VR700") (pin "E") (pinfunction "C_E") (pintype "passive"))
      (node (ref "VR7K") (pin "3") (pinfunction "A_3") (pintype "passive"))
      (node (ref "VR7K") (pin "E") (pinfunction "C_E") (pintype "passive"))
    )
    (net (code "9") (name "H") (class "Default")
      (node (ref "2K") (pin "P$1_TIP") (pinfunction "TIP_P$1_TIP") (pintype "passive"))
      (node (ref "R27") (pin "2") (pinfunction "2_2") (pintype "passive"))
      (node (ref "VR2K") (pin "1") (pinfunction "E_1") (pintype "passive"))
    )
    (net (code "10") (name "I") (class "Default")
      (node (ref "3.5K") (pin "P$1_TIP") (pinfunction "TIP_P$1_TIP") (pintype "passive"))
      (node (ref "R47") (pin "2") (pinfunction "2_2") (pintype "passive"))
      (node (ref "VR3.5K") (pin "1") (pinfunction "E_1") (pintype "passive"))
    )
    (net (code "11") (name "J") (class "Default")
      (node (ref ">7K") (pin "P$1_TIP") (pinfunction "TIP_P$1_TIP") (pintype "passive"))
      (node (ref "R42") (pin "2") (pinfunction "2_2") (pintype "passive"))
      (node (ref "VR7K") (pin "1") (pinfunction "E_1") (pintype "passive"))
    )
    (net (code "12") (name "K") (class "Default")
      (node (ref "C20") (pin "1") (pinfunction "1_1") (pintype "passive"))
      (node (ref "R51") (pin "1") (pinfunction "1_1") (pintype "passive"))
      (node (ref "R52") (pin "1") (pinfunction "1_1") (pintype "passive"))
      (node (ref "R53") (pin "1") (pinfunction "1_1") (pintype "passive"))
      (node (ref "R54") (pin "1") (pinfunction "1_1") (pintype "passive"))
      (node (ref "R55") (pin "1") (pinfunction "1_1") (pintype "passive"))
      (node (ref "R56") (pin "1") (pinfunction "1_1") (pintype "passive"))
      (node (ref "R57") (pin "1") (pinfunction "1_1") (pintype "passive"))
      (node (ref "R58") (pin "1") (pinfunction "1_1") (pintype "passive"))
      (node (ref "R59") (pin "1") (pinfunction "1_1") (pintype "passive"))
      (node (ref "R60") (pin "1") (pinfunction "1_1") (pintype "passive"))
      (node (ref "R61") (pin "2") (pinfunction "2_2") (pintype "passive"))
      (node (ref "U16") (pin "2") (pinfunction "-IN_2") (pintype "input"))
    )
    (net (code "13") (name "Net-(C3-Pad1)") (class "Default")
      (node (ref "C3") (pin "1") (pinfunction "1_1") (pintype "passive"))
      (node (ref "R7") (pin "2") (pinfunction "2_2") (pintype "passive"))
      (node (ref "R8") (pin "1") (pinfunction "1_1") (pintype "passive"))
    )
    (net (code "14") (name "Net-(C4-Pad1)") (class "Default")
      (node (ref "C4") (pin "1") (pinfunction "1_1") (pintype "passive"))
      (node (ref "R8") (pin "2") (pinfunction "2_2") (pintype "passive"))
      (node (ref "R9") (pin "1") (pinfunction "1_1") (pintype "passive"))
    )
    (net (code "15") (name "Net-(C7-Pad2)") (class "Default")
      (node (ref "C7") (pin "2") (pinfunction "2_2") (pintype "passive"))
      (node (ref "R13") (pin "1") (pinfunction "1_1") (pintype "passive"))
      (node (ref "VR2") (pin "A") (pinfunction "A_A") (pintype "passive"))
      (node (ref "VR2") (pin "S") (pinfunction "S_S") (pintype "passive"))
    )
    (net (code "16") (name "Net-(C8-Pad1)") (class "Default")
      (node (ref "C8") (pin "1") (pinfunction "1_1") (pintype "passive"))
      (node (ref "C9") (pin "1") (pinfunction "1_1") (pintype "passive"))
      (node (ref "R12") (pin "2") (pinfunction "2_2") (pintype "passive"))
    )
    (net (code "17") (name "Net-(C10-Pad2)") (class "Default")
      (node (ref "C10") (pin "2") (pinfunction "2_2") (pintype "passive"))
      (node (ref "R17") (pin "1") (pinfunction "1_1") (pintype "passive"))
      (node (ref "VR4") (pin "A") (pinfunction "A_A") (pintype "passive"))
      (node (ref "VR4") (pin "S") (pinfunction "S_S") (pintype "passive"))
    )
    (net (code "18") (name "Net-(C11-Pad1)") (class "Default")
      (node (ref "C11") (pin "1") (pinfunction "1_1") (pintype "passive"))
      (node (ref "C12") (pin "1") (pinfunction "1_1") (pintype "passive"))
      (node (ref "R16") (pin "2") (pinfunction "2_2") (pintype "passive"))
    )
    (net (code "19") (name "Net-(C13-Pad2)") (class "Default")
      (node (ref "C13") (pin "2") (pinfunction "2_2") (pintype "passive"))
      (node (ref "R19") (pin "1") (pinfunction "1_1") (pintype "passive"))
      (node (ref "VR6") (pin "A") (pinfunction "A_A") (pintype "passive"))
      (node (ref "VR6") (pin "S") (pinfunction "S_S") (pintype "passive"))
    )
    (net (code "20") (name "Net-(C14-Pad1)") (class "Default")
      (node (ref "C14") (pin "1") (pinfunction "1_1") (pintype "passive"))
      (node (ref "C15") (pin "1") (pinfunction "1_1") (pintype "passive"))
      (node (ref "R18") (pin "2") (pinfunction "2_2") (pintype "passive"))
    )
    (net (code "21") (name "Net-(C16-Pad2)") (class "Default")
      (node (ref "C16") (pin "2") (pinfunction "2_2") (pintype "passive"))
      (node (ref "R25") (pin "1") (pinfunction "1_1") (pintype "passive"))
      (node (ref "VR8") (pin "A") (pinfunction "A_A") (pintype "passive"))
      (node (ref "VR8") (pin "S") (pinfunction "S_S") (pintype "passive"))
    )
    (net (code "22") (name "Net-(C17-Pad1)") (class "Default")
      (node (ref "C17") (pin "1") (pinfunction "1_1") (pintype "passive"))
      (node (ref "C18") (pin "1") (pinfunction "1_1") (pintype "passive"))
      (node (ref "R24") (pin "2") (pinfunction "2_2") (pintype "passive"))
    )
    (net (code "23") (name "Net-(C19-Pad2)") (class "Default")
      (node (ref "C19") (pin "2") (pinfunction "2_2") (pintype "passive"))
      (node (ref "C21") (pin "1") (pinfunction "1_1") (pintype "passive"))
      (node (ref "R30") (pin "2") (pinfunction "2_2") (pintype "passive"))
    )
    (net (code "24") (name "Net-(C21-Pad2)") (class "Default")
      (node (ref "C21") (pin "2") (pinfunction "2_2") (pintype "passive"))
      (node (ref "C35") (pin "1") (pinfunction "1_1") (pintype "passive"))
      (node (ref "R29") (pin "2") (pinfunction "2_2") (pintype "passive"))
    )
    (net (code "25") (name "Net-(C22-Pad2)") (class "Default")
      (node (ref "C22") (pin "2") (pinfunction "2_2") (pintype "passive"))
      (node (ref "R33") (pin "1") (pinfunction "1_1") (pintype "passive"))
      (node (ref "VR10") (pin "A") (pinfunction "A_A") (pintype "passive"))
      (node (ref "VR10") (pin "S") (pinfunction "S_S") (pintype "passive"))
    )
    (net (code "26") (name "Net-(C23-Pad1)") (class "Default")
      (node (ref "C23") (pin "1") (pinfunction "1_1") (pintype "passive"))
      (node (ref "C24") (pin "1") (pinfunction "1_1") (pintype "passive"))
      (node (ref "R32") (pin "2") (pinfunction "2_2") (pintype "passive"))
    )
    (net (code "27") (name "Net-(C25-Pad2)") (class "Default")
      (node (ref "C25") (pin "2") (pinfunction "2_2") (pintype "passive"))
      (node (ref "R35") (pin "1") (pinfunction "1_1") (pintype "passive"))
      (node (ref "VR12") (pin "A") (pinfunction "A_A") (pintype "passive"))
      (node (ref "VR12") (pin "S") (pinfunction "S_S") (pintype "passive"))
    )
    (net (code "28") (name "Net-(C26-Pad1)") (class "Default")
      (node (ref "C26") (pin "1") (pinfunction "1_1") (pintype "passive"))
      (node (ref "C27") (pin "1") (pinfunction "1_1") (pintype "passive"))
      (node (ref "R34") (pin "2") (pinfunction "2_2") (pintype "passive"))
    )
    (net (code "29") (name "Net-(C28-Pad2)") (class "Default")
      (node (ref "C28") (pin "2") (pinfunction "2_2") (pintype "passive"))
      (node (ref "R37") (pin "1") (pinfunction "1_1") (pintype "passive"))
      (node (ref "VR14") (pin "A") (pinfunction "A_A") (pintype "passive"))
      (node (ref "VR14") (pin "S") (pinfunction "S_S") (pintype "passive"))
    )
    (net (code "30") (name "Net-(C29-Pad1)") (class "Default")
      (node (ref "C29") (pin "1") (pinfunction "1_1") (pintype "passive"))
      (node (ref "C30") (pin "1") (pinfunction "1_1") (pintype "passive"))
      (node (ref "R36") (pin "2") (pinfunction "2_2") (pintype "passive"))
    )
    (net (code "31") (name "Net-(C31-Pad2)") (class "Default")
      (node (ref "C31") (pin "2") (pinfunction "2_2") (pintype "passive"))
      (node (ref "R39") (pin "1") (pinfunction "1_1") (pintype "passive"))
      (node (ref "VR16") (pin "A") (pinfunction "A_A") (pintype "passive"))
      (node (ref "VR16") (pin "S") (pinfunction "S_S") (pintype "passive"))
    )
    (net (code "32") (name "Net-(C32-Pad1)") (class "Default")
      (node (ref "C32") (pin "1") (pinfunction "1_1") (pintype "passive"))
      (node (ref "C33") (pin "1") (pinfunction "1_1") (pintype "passive"))
      (node (ref "R38") (pin "2") (pinfunction "2_2") (pintype "passive"))
    )
    (net (code "33") (name "Net-(C36-Pad2)") (class "Default")
      (node (ref "C36") (pin "2") (pinfunction "2_2") (pintype "passive"))
      (node (ref "R62") (pin "2") (pinfunction "2_2") (pintype "passive"))
    )
    (net (code "34") (name "Net-(C55-Pad1)") (class "Default")
      (node (ref "C55") (pin "1") (pinfunction "1_1") (pintype "passive"))
      (node (ref "R1") (pin "1") (pinfunction "1_1") (pintype "passive"))
    )
    (net (code "35") (name "Net-(D1-PadC)") (class "Default")
      (node (ref "D1") (pin "C") (pinfunction "C_C") (pintype "passive"))
      (node (ref "JP2") (pin "1") (pinfunction "1_1") (pintype "passive"))
      (node (ref "JP2") (pin "2") (pinfunction "2_2") (pintype "passive"))
    )
    (net (code "36") (name "Net-(D2-PadA)") (class "Default")
      (node (ref "D2") (pin "A") (pinfunction "A_A") (pintype "passive"))
      (node (ref "JP2") (pin "10") (pinfunction "10_10") (pintype "passive"))
      (node (ref "JP2") (pin "9") (pinfunction "9_9") (pintype "passive"))
    )
    (net (code "37") (name "Net-(IN-TIP)") (class "Default")
      (node (ref "C55") (pin "2") (pinfunction "2_2") (pintype "passive"))
      (node (ref "IN") (pin "P$1_TIP") (pinfunction "TIP_P$1_TIP") (pintype "passive"))
    )
    (net (code "38") (name "Net-(R13-Pad2)") (class "Default")
      (node (ref "R13") (pin "2") (pinfunction "2_2") (pintype "passive"))
      (node (ref "VR1") (pin "S") (pinfunction "S_S") (pintype "passive"))
    )
    (net (code "39") (name "Net-(R17-Pad2)") (class "Default")
      (node (ref "R17") (pin "2") (pinfunction "2_2") (pintype "passive"))
      (node (ref "VR3") (pin "S") (pinfunction "S_S") (pintype "passive"))
    )
    (net (code "40") (name "Net-(R19-Pad2)") (class "Default")
      (node (ref "R19") (pin "2") (pinfunction "2_2") (pintype "passive"))
      (node (ref "VR5") (pin "S") (pinfunction "S_S") (pintype "passive"))
    )
    (net (code "41") (name "Net-(R25-Pad2)") (class "Default")
      (node (ref "R25") (pin "2") (pinfunction "2_2") (pintype "passive"))
      (node (ref "VR7") (pin "S") (pinfunction "S_S") (pintype "passive"))
    )
    (net (code "42") (name "Net-(R33-Pad2)") (class "Default")
      (node (ref "R33") (pin "2") (pinfunction "2_2") (pintype "passive"))
      (node (ref "VR9") (pin "S") (pinfunction "S_S") (pintype "passive"))
    )
    (net (code "43") (name "Net-(R35-Pad2)") (class "Default")
      (node (ref "R35") (pin "2") (pinfunction "2_2") (pintype "passive"))
      (node (ref "VR11") (pin "S") (pinfunction "S_S") (pintype "passive"))
    )
    (net (code "44") (name "Net-(R37-Pad2)") (class "Default")
      (node (ref "R37") (pin "2") (pinfunction "2_2") (pintype "passive"))
      (node (ref "VR13") (pin "S") (pinfunction "S_S") (pintype "passive"))
    )
    (net (code "45") (name "Net-(R39-Pad2)") (class "Default")
      (node (ref "R39") (pin "2") (pinfunction "2_2") (pintype "passive"))
      (node (ref "VR15") (pin "S") (pinfunction "S_S") (pintype "passive"))
    )
    (net (code "46") (name "Net-(SUM_OUT-TIP)") (class "Default")
      (node (ref "R67") (pin "1") (pinfunction "1_1") (pintype "passive"))
      (node (ref "SUM_OUT") (pin "P$1_TIP") (pinfunction "TIP_P$1_TIP") (pintype "passive"))
    )
    (net (code "47") (name "Net-(U2A-+IN)") (class "Default")
      (node (ref "R3") (pin "2") (pinfunction "2_2") (pintype "passive"))
      (node (ref "U2") (pin "3") (pinfunction "+IN_3") (pintype "input"))
    )
    (net (code "48") (name "Net-(U2A--IN)") (class "Default")
      (node (ref "C1") (pin "2") (pinfunction "2_2") (pintype "passive"))
      (node (ref "R1") (pin "2") (pinfunction "2_2") (pintype "passive"))
      (node (ref "R2") (pin "1") (pinfunction "1_1") (pintype "passive"))
      (node (ref "U2") (pin "2") (pinfunction "-IN_2") (pintype "input"))
    )
    (net (code "49") (name "Net-(U2A-OUT)") (class "Default")
      (node (ref "C1") (pin "1") (pinfunction "1_1") (pintype "passive"))
      (node (ref "C10") (pin "1") (pinfunction "1_1") (pintype "passive"))
      (node (ref "C13") (pin "1") (pinfunction "1_1") (pintype "passive"))
      (node (ref "C16") (pin "1") (pinfunction "1_1") (pintype "passive"))
      (node (ref "C7") (pin "1") (pinfunction "1_1") (pintype "passive"))
      (node (ref "R12") (pin "1") (pinfunction "1_1") (pintype "passive"))
      (node (ref "R16") (pin "1") (pinfunction "1_1") (pintype "passive"))
      (node (ref "R18") (pin "1") (pinfunction "1_1") (pintype "passive"))
      (node (ref "R2") (pin "2") (pinfunction "2_2") (pintype "passive"))
      (node (ref "R24") (pin "1") (pinfunction "1_1") (pintype "passive"))
      (node (ref "R28") (pin "2") (pinfunction "2_2") (pintype "passive"))
      (node (ref "R4") (pin "2") (pinfunction "2_2") (pintype "passive"))
      (node (ref "R7") (pin "1") (pinfunction "1_1") (pintype "passive"))
      (node (ref "U2") (pin "1") (pinfunction "OUT_1") (pintype "output"))
    )
    (net (code "50") (name "Net-(U2B-+IN)") (class "Default")
      (node (ref "R6") (pin "1") (pinfunction "1_1") (pintype "passive"))
      (node (ref "U2") (pin "5") (pinfunction "+IN_5") (pintype "input"))
    )
    (net (code "51") (name "Net-(U2B--IN)") (class "Default")
      (node (ref "C2") (pin "2") (pinfunction "2_2") (pintype "passive"))
      (node (ref "R4") (pin "1") (pinfunction "1_1") (pintype "passive"))
      (node (ref "R5") (pin "2") (pinfunction "2_2") (pintype "passive"))
      (node (ref "U2") (pin "6") (pinfunction "-IN_6") (pintype "input"))
    )
    (net (code "52") (name "Net-(U2B-OUT)") (class "Default")
      (node (ref "C19") (pin "1") (pinfunction "1_1") (pintype "passive"))
      (node (ref "C2") (pin "1") (pinfunction "1_1") (pintype "passive"))
      (node (ref "C22") (pin "1") (pinfunction "1_1") (pintype "passive"))
      (node (ref "C25") (pin "1") (pinfunction "1_1") (pintype "passive"))
      (node (ref "C28") (pin "1") (pinfunction "1_1") (pintype "passive"))
      (node (ref "C31") (pin "1") (pinfunction "1_1") (pintype "passive"))
      (node (ref "R32") (pin "1") (pinfunction "1_1") (pintype "passive"))
      (node (ref "R34") (pin "1") (pinfunction "1_1") (pintype "passive"))
      (node (ref "R36") (pin "1") (pinfunction "1_1") (pintype "passive"))
      (node (ref "R38") (pin "1") (pinfunction "1_1") (pintype "passive"))
      (node (ref "R40") (pin "2") (pinfunction "2_2") (pintype "passive"))
      (node (ref "R5") (pin "1") (pinfunction "1_1") (pintype "passive"))
      (node (ref "U2") (pin "7") (pinfunction "OUT_7") (pintype "output"))
    )
    (net (code "53") (name "Net-(U3A-+IN)") (class "Default")
      (node (ref "R26") (pin "2") (pinfunction "2_2") (pintype "passive"))
      (node (ref "U3") (pin "3") (pinfunction "+IN_3") (pintype "input"))
    )
    (net (code "54") (name "Net-(U3A--IN)") (class "Default")
      (node (ref "C17") (pin "2") (pinfunction "2_2") (pintype "passive"))
      (node (ref "U3") (pin "2") (pinfunction "-IN_2") (pintype "input"))
      (node (ref "VR7") (pin "E") (pinfunction "E_E") (pintype "passive"))
    )
    (net (code "55") (name "Net-(U3A-OUT)") (class "Default")
      (node (ref "C18") (pin "2") (pinfunction "2_2") (pintype "passive"))
      (node (ref "R27") (pin "1") (pinfunction "1_1") (pintype "passive"))
      (node (ref "U3") (pin "1") (pinfunction "OUT_1") (pintype "output"))
      (node (ref "VR8") (pin "E") (pinfunction "E_E") (pintype "passive"))
    )
    (net (code "56") (name "Net-(U3B-+IN)") (class "Default")
      (node (ref "R43") (pin "2") (pinfunction "2_2") (pintype "passive"))
      (node (ref "U3") (pin "5") (pinfunction "+IN_5") (pintype "input"))
    )
    (net (code "57") (name "Net-(U3B--IN)") (class "Default")
      (node (ref "C23") (pin "2") (pinfunction "2_2") (pintype "passive"))
      (node (ref "U3") (pin "6") (pinfunction "-IN_6") (pintype "input"))
      (node (ref "VR9") (pin "E") (pinfunction "E_E") (pintype "passive"))
    )
    (net (code "58") (name "Net-(U3B-OUT)") (class "Default")
      (node (ref "C24") (pin "2") (pinfunction "2_2") (pintype "passive"))
      (node (ref "R47") (pin "1") (pinfunction "1_1") (pintype "passive"))
      (node (ref "U3") (pin "7") (pinfunction "OUT_7") (pintype "output"))
      (node (ref "VR10") (pin "E") (pinfunction "E_E") (pintype "passive"))
    )
    (net (code "59") (name "Net-(U3C-+IN)") (class "Default")
      (node (ref "C35") (pin "2") (pinfunction "2_2") (pintype "passive"))
      (node (ref "R31") (pin "2") (pinfunction "2_2") (pintype "passive"))
      (node (ref "U3") (pin "10") (pinfunction "+IN_10") (pintype "input"))
    )
    (net (code "60") (name "Net-(U3C--IN)") (class "Default")
      (node (ref "C34") (pin "1") (pinfunction "1_1") (pintype "passive"))
      (node (ref "R41") (pin "1") (pinfunction "1_1") (pintype "passive"))
      (node (ref "U3") (pin "9") (pinfunction "-IN_9") (pintype "input"))
    )
    (net (code "61") (name "Net-(U3C-OUT)") (class "Default")
      (node (ref "C34") (pin "2") (pinfunction "2_2") (pintype "passive"))
      (node (ref "R29") (pin "1") (pinfunction "1_1") (pintype "passive"))
      (node (ref "R41") (pin "2") (pinfunction "2_2") (pintype "passive"))
      (node (ref "R42") (pin "1") (pinfunction "1_1") (pintype "passive"))
      (node (ref "U3") (pin "8") (pinfunction "OUT_8") (pintype "output"))
    )
    (net (code "62") (name "Net-(U3D-+IN)") (class "Default")
      (node (ref "R44") (pin "2") (pinfunction "2_2") (pintype "passive"))
      (node (ref "U3") (pin "12") (pinfunction "+IN_12") (pintype "input"))
    )
    (net (code "63") (name "Net-(U3D--IN)") (class "Default")
      (node (ref "C26") (pin "2") (pinfunction "2_2") (pintype "passive"))
      (node (ref "U3") (pin "13") (pinfunction "-IN_13") (pintype "input"))
      (node (ref "VR11") (pin "E") (pinfunction "E_E") (pintype "passive"))
    )
    (net (code "64") (name "Net-(U3D-OUT)") (class "Default")
      (node (ref "C27") (pin "2") (pinfunction "2_2") (pintype "passive"))
      (node (ref "R48") (pin "1") (pinfunction "1_1") (pintype "passive"))
      (node (ref "U3") (pin "14") (pinfunction "OUT_14") (pintype "output"))
      (node (ref "VR12") (pin "E") (pinfunction "E_E") (pintype "passive"))
    )
    (net (code "65") (name "Net-(U4A-+IN)") (class "Default")
      (node (ref "R14") (pin "2") (pinfunction "2_2") (pintype "passive"))
      (node (ref "U4") (pin "3") (pinfunction "+IN_3") (pintype "input"))
    )
    (net (code "66") (name "Net-(U4A--IN)") (class "Default")
      (node (ref "C8") (pin "2") (pinfunction "2_2") (pintype "passive"))
      (node (ref "U4") (pin "2") (pinfunction "-IN_2") (pintype "input"))
      (node (ref "VR1") (pin "E") (pinfunction "E_E") (pintype "passive"))
    )
    (net (code "67") (name "Net-(U4A-OUT)") (class "Default")
      (node (ref "C9") (pin "2") (pinfunction "2_2") (pintype "passive"))
      (node (ref "R15") (pin "1") (pinfunction "1_1") (pintype "passive"))
      (node (ref "U4") (pin "1") (pinfunction "OUT_1") (pintype "output"))
      (node (ref "VR2") (pin "E") (pinfunction "E_E") (pintype "passive"))
    )
    (net (code "68") (name "Net-(U4B-+IN)") (class "Default")
      (node (ref "R46") (pin "2") (pinfunction "2_2") (pintype "passive"))
      (node (ref "U4") (pin "5") (pinfunction "+IN_5") (pintype "input"))
    )
    (net (code "69") (name "Net-(U4B--IN)") (class "Default")
      (node (ref "C32") (pin "2") (pinfunction "2_2") (pintype "passive"))
      (node (ref "U4") (pin "6") (pinfunction "-IN_6") (pintype "input"))
      (node (ref "VR15") (pin "E") (pinfunction "E_E") (pintype "passive"))
    )
    (net (code "70") (name "Net-(U4B-OUT)") (class "Default")
      (node (ref "C33") (pin "2") (pinfunction "2_2") (pintype "passive"))
      (node (ref "R50") (pin "1") (pinfunction "1_1") (pintype "passive"))
      (node (ref "U4") (pin "7") (pinfunction "OUT_7") (pintype "output"))
      (node (ref "VR16") (pin "E") (pinfunction "E_E") (pintype "passive"))
    )
    (net (code "71") (name "Net-(U4C-+IN)") (class "Default")
      (node (ref "R20") (pin "2") (pinfunction "2_2") (pintype "passive"))
      (node (ref "U4") (pin "10") (pinfunction "+IN_10") (pintype "input"))
    )
    (net (code "72") (name "Net-(U4C--IN)") (class "Default")
      (node (ref "C11") (pin "2") (pinfunction "2_2") (pintype "passive"))
      (node (ref "U4") (pin "9") (pinfunction "-IN_9") (pintype "input"))
      (node (ref "VR3") (pin "E") (pinfunction "E_E") (pintype "passive"))
    )
    (net (code "73") (name "Net-(U4C-OUT)") (class "Default")
      (node (ref "C12") (pin "2") (pinfunction "2_2") (pintype "passive"))
      (node (ref "R22") (pin "1") (pinfunction "1_1") (pintype "passive"))
      (node (ref "U4") (pin "8") (pinfunction "OUT_8") (pintype "output"))
      (node (ref "VR4") (pin "E") (pinfunction "E_E") (pintype "passive"))
    )
    (net (code "74") (name "Net-(U4D-+IN)") (class "Default")
      (node (ref "C5") (pin "1") (pinfunction "1_1") (pintype "passive"))
      (node (ref "R9") (pin "2") (pinfunction "2_2") (pintype "passive"))
      (node (ref "U4") (pin "12") (pinfunction "+IN_12") (pintype "input"))
    )
    (net (code "75") (name "Net-(U4D--IN)") (class "Default")
      (node (ref "C6") (pin "1") (pinfunction "1_1") (pintype "passive"))
      (node (ref "R10") (pin "1") (pinfunction "1_1") (pintype "passive"))
      (node (ref "U4") (pin "13") (pinfunction "-IN_13") (pintype "input"))
    )
    (net (code "76") (name "Net-(U4D-OUT)") (class "Default")
      (node (ref "C4") (pin "2") (pinfunction "2_2") (pintype "passive"))
      (node (ref "C6") (pin "2") (pinfunction "2_2") (pintype "passive"))
      (node (ref "R10") (pin "2") (pinfunction "2_2") (pintype "passive"))
      (node (ref "R11") (pin "1") (pinfunction "1_1") (pintype "passive"))
      (node (ref "U4") (pin "14") (pinfunction "OUT_14") (pintype "output"))
    )
    (net (code "77") (name "Net-(U5A-+IN)") (class "Default")
      (node (ref "R21") (pin "2") (pinfunction "2_2") (pintype "passive"))
      (node (ref "U5") (pin "3") (pinfunction "+IN_3") (pintype "input"))
    )
    (net (code "78") (name "Net-(U5A--IN)") (class "Default")
      (node (ref "C14") (pin "2") (pinfunction "2_2") (pintype "passive"))
      (node (ref "U5") (pin "2") (pinfunction "-IN_2") (pintype "input"))
      (node (ref "VR5") (pin "E") (pinfunction "E_E") (pintype "passive"))
    )
    (net (code "79") (name "Net-(U5A-OUT)") (class "Default")
      (node (ref "C15") (pin "2") (pinfunction "2_2") (pintype "passive"))
      (node (ref "R23") (pin "1") (pinfunction "1_1") (pintype "passive"))
      (node (ref "U5") (pin "1") (pinfunction "OUT_1") (pintype "output"))
      (node (ref "VR6") (pin "E") (pinfunction "E_E") (pintype "passive"))
    )
    (net (code "80") (name "Net-(U5B-+IN)") (class "Default")
      (node (ref "R45") (pin "2") (pinfunction "2_2") (pintype "passive"))
      (node (ref "U5") (pin "5") (pinfunction "+IN_5") (pintype "input"))
    )
    (net (code "81") (name "Net-(U5B--IN)") (class "Default")
      (node (ref "C29") (pin "2") (pinfunction "2_2") (pintype "passive"))
      (node (ref "U5") (pin "6") (pinfunction "-IN_6") (pintype "input"))
      (node (ref "VR13") (pin "E") (pinfunction "E_E") (pintype "passive"))
    )
    (net (code "82") (name "Net-(U5B-OUT)") (class "Default")
      (node (ref "C30") (pin "2") (pinfunction "2_2") (pintype "passive"))
      (node (ref "R49") (pin "1") (pinfunction "1_1") (pintype "passive"))
      (node (ref "U5") (pin "7") (pinfunction "OUT_7") (pintype "output"))
      (node (ref "VR14") (pin "E") (pinfunction "E_E") (pintype "passive"))
    )
    (net (code "83") (name "Net-(U16A-+IN)") (class "Default")
      (node (ref "R65") (pin "1") (pinfunction "1_1") (pintype "passive"))
      (node (ref "U16") (pin "3") (pinfunction "+IN_3") (pintype "input"))
    )
    (net (code "84") (name "Net-(U16A-OUT)") (class "Default")
      (node (ref "C20") (pin "2") (pinfunction "2_2") (pintype "passive"))
      (node (ref "C36") (pin "1") (pinfunction "1_1") (pintype "passive"))
      (node (ref "R61") (pin "1") (pinfunction "1_1") (pintype "passive"))
      (node (ref "U16") (pin "1") (pinfunction "OUT_1") (pintype "output"))
    )
    (net (code "85") (name "Net-(U16B-+IN)") (class "Default")
      (node (ref "R66") (pin "1") (pinfunction "1_1") (pintype "passive"))
      (node (ref "U16") (pin "5") (pinfunction "+IN_5") (pintype "input"))
    )
    (net (code "86") (name "Net-(U16B--IN)") (class "Default")
      (node (ref "C37") (pin "1") (pinfunction "1_1") (pintype "passive"))
      (node (ref "R62") (pin "1") (pinfunction "1_1") (pintype "passive"))
      (node (ref "R63") (pin "2") (pinfunction "2_2") (pintype "passive"))
      (node (ref "R64") (pin "2") (pinfunction "2_2") (pintype "passive"))
      (node (ref "U16") (pin "6") (pinfunction "-IN_6") (pintype "input"))
    )
    (net (code "87") (name "Net-(U16B-OUT)") (class "Default")
      (node (ref "C37") (pin "2") (pinfunction "2_2") (pintype "passive"))
      (node (ref "R63") (pin "1") (pinfunction "1_1") (pintype "passive"))
      (node (ref "R64") (pin "1") (pinfunction "1_1") (pintype "passive"))
      (node (ref "R67") (pin "2") (pinfunction "2_2") (pintype "passive"))
      (node (ref "U16") (pin "7") (pinfunction "OUT_7") (pintype "output"))
    )
    (net (code "88") (name "Net-(VR1.4KA-S)") (class "Default")
      (node (ref "R57") (pin "2") (pinfunction "2_2") (pintype "passive"))
      (node (ref "VR1.4K") (pin "2") (pinfunction "S_2") (pintype "passive"))
    )
    (net (code "89") (name "Net-(VR1.4KB-A)") (class "Default")
      (node (ref "R75") (pin "1") (pinfunction "1_1") (pintype "passive"))
      (node (ref "VR1.4K") (pin "B") (pinfunction "A_B") (pintype "passive"))
    )
    (net (code "90") (name "Net-(VR1KA-S)") (class "Default")
      (node (ref "R56") (pin "2") (pinfunction "2_2") (pintype "passive"))
      (node (ref "VR1K") (pin "2") (pinfunction "S_2") (pintype "passive"))
    )
    (net (code "91") (name "Net-(VR1KB-A)") (class "Default")
      (node (ref "R74") (pin "1") (pinfunction "1_1") (pintype "passive"))
      (node (ref "VR1K") (pin "B") (pinfunction "A_B") (pintype "passive"))
    )
    (net (code "92") (name "Net-(VR2KA-S)") (class "Default")
      (node (ref "R58") (pin "2") (pinfunction "2_2") (pintype "passive"))
      (node (ref "VR2K") (pin "2") (pinfunction "S_2") (pintype "passive"))
    )
    (net (code "93") (name "Net-(VR2KB-A)") (class "Default")
      (node (ref "R76") (pin "1") (pinfunction "1_1") (pintype "passive"))
      (node (ref "VR2K") (pin "B") (pinfunction "A_B") (pintype "passive"))
    )
    (net (code "94") (name "Net-(VR3.5KA-S)") (class "Default")
      (node (ref "R59") (pin "2") (pinfunction "2_2") (pintype "passive"))
      (node (ref "VR3.5K") (pin "2") (pinfunction "S_2") (pintype "passive"))
    )
    (net (code "95") (name "Net-(VR3.5KB-A)") (class "Default")
      (node (ref "R77") (pin "1") (pinfunction "1_1") (pintype "passive"))
      (node (ref "VR3.5K") (pin "B") (pinfunction "A_B") (pintype "passive"))
    )
    (net (code "96") (name "Net-(VR7KA-S)") (class "Default")
      (node (ref "R60") (pin "2") (pinfunction "2_2") (pintype "passive"))
      (node (ref "VR7K") (pin "2") (pinfunction "S_2") (pintype "passive"))
    )
    (net (code "97") (name "Net-(VR7KB-A)") (class "Default")
      (node (ref "R78") (pin "1") (pinfunction "1_1") (pintype "passive"))
      (node (ref "VR7K") (pin "B") (pinfunction "A_B") (pintype "passive"))
    )
    (net (code "98") (name "Net-(VR100A-S)") (class "Default")
      (node (ref "R51") (pin "2") (pinfunction "2_2") (pintype "passive"))
      (node (ref "VR100") (pin "2") (pinfunction "S_2") (pintype "passive"))
    )
    (net (code "99") (name "Net-(VR100B-A)") (class "Default")
      (node (ref "R69") (pin "1") (pinfunction "1_1") (pintype "passive"))
      (node (ref "VR100") (pin "B") (pinfunction "A_B") (pintype "passive"))
    )
    (net (code "100") (name "Net-(VR200A-S)") (class "Default")
      (node (ref "R52") (pin "2") (pinfunction "2_2") (pintype "passive"))
      (node (ref "VR200") (pin "2") (pinfunction "S_2") (pintype "passive"))
    )
    (net (code "101") (name "Net-(VR200B-A)") (class "Default")
      (node (ref "R70") (pin "1") (pinfunction "1_1") (pintype "passive"))
      (node (ref "VR200") (pin "B") (pinfunction "A_B") (pintype "passive"))
    )
    (net (code "102") (name "Net-(VR350A-S)") (class "Default")
      (node (ref "R53") (pin "2") (pinfunction "2_2") (pintype "passive"))
      (node (ref "VR350") (pin "2") (pinfunction "S_2") (pintype "passive"))
    )
    (net (code "103") (name "Net-(VR350B-A)") (class "Default")
      (node (ref "R71") (pin "1") (pinfunction "1_1") (pintype "passive"))
      (node (ref "VR350") (pin "B") (pinfunction "A_B") (pintype "passive"))
    )
    (net (code "104") (name "Net-(VR500A-S)") (class "Default")
      (node (ref "R54") (pin "2") (pinfunction "2_2") (pintype "passive"))
      (node (ref "VR500") (pin "2") (pinfunction "S_2") (pintype "passive"))
    )
    (net (code "105") (name "Net-(VR500B-A)") (class "Default")
      (node (ref "R72") (pin "1") (pinfunction "1_1") (pintype "passive"))
      (node (ref "VR500") (pin "B") (pinfunction "A_B") (pintype "passive"))
    )
    (net (code "106") (name "Net-(VR700A-S)") (class "Default")
      (node (ref "R55") (pin "2") (pinfunction "2_2") (pintype "passive"))
      (node (ref "VR700") (pin "2") (pinfunction "S_2") (pintype "passive"))
    )
    (net (code "107") (name "Net-(VR700B-A)") (class "Default")
      (node (ref "R73") (pin "1") (pinfunction "1_1") (pintype "passive"))
      (node (ref "VR700") (pin "B") (pinfunction "A_B") (pintype "passive"))
    )
    (net (code "108") (name "VCC") (class "Default")
      (node (ref "C39") (pin "+") (pinfunction "+_+") (pintype "passive"))
      (node (ref "C41") (pin "+") (pinfunction "+_+") (pintype "passive"))
      (node (ref "C43") (pin "1") (pinfunction "1_1") (pintype "passive"))
      (node (ref "C45") (pin "1") (pinfunction "1_1") (pintype "passive"))
      (node (ref "C47") (pin "1") (pinfunction "1_1") (pintype "passive"))
      (node (ref "C49") (pin "1") (pinfunction "1_1") (pintype "passive"))
      (node (ref "C51") (pin "1") (pinfunction "1_1") (pintype "passive"))
      (node (ref "D2") (pin "C") (pinfunction "C_C") (pintype "passive"))
      (node (ref "R69") (pin "2") (pinfunction "2_2") (pintype "passive"))
      (node (ref "R70") (pin "2") (pinfunction "2_2") (pintype "passive"))
      (node (ref "R71") (pin "2") (pinfunction "2_2") (pintype "passive"))
      (node (ref "R72") (pin "2") (pinfunction "2_2") (pintype "passive"))
      (node (ref "R73") (pin "2") (pinfunction "2_2") (pintype "passive"))
      (node (ref "R74") (pin "2") (pinfunction "2_2") (pintype "passive"))
      (node (ref "R75") (pin "2") (pinfunction "2_2") (pintype "passive"))
      (node (ref "R76") (pin "2") (pinfunction "2_2") (pintype "passive"))
      (node (ref "R77") (pin "2") (pinfunction "2_2") (pintype "passive"))
      (node (ref "R78") (pin "2") (pinfunction "2_2") (pintype "passive"))
      (node (ref "U16") (pin "8") (pinfunction "V+_8") (pintype "power_in"))
      (node (ref "U2") (pin "8") (pinfunction "V+_8") (pintype "power_in"))
      (node (ref "U3") (pin "4") (pinfunction "V+_4") (pintype "power_in"))
      (node (ref "U4") (pin "4") (pinfunction "V+_4") (pintype "power_in"))
      (node (ref "U5") (pin "8") (pinfunction "V+_8") (pintype "power_in"))
    )
    (net (code "109") (name "VEE") (class "Default")
      (node (ref "C38") (pin "-") (pinfunction "-_-") (pintype "passive"))
      (node (ref "C40") (pin "-") (pinfunction "-_-") (pintype "passive"))
      (node (ref "C42") (pin "2") (pinfunction "2_2") (pintype "passive"))
      (node (ref "C44") (pin "2") (pinfunction "2_2") (pintype "passive"))
      (node (ref "C46") (pin "2") (pinfunction "2_2") (pintype "passive"))
      (node (ref "C48") (pin "2") (pinfunction "2_2") (pintype "passive"))
      (node (ref "C50") (pin "2") (pinfunction "2_2") (pintype "passive"))
      (node (ref "D1") (pin "A") (pinfunction "A_A") (pintype "passive"))
      (node (ref "U16") (pin "4") (pinfunction "V-_4") (pintype "power_in"))
      (node (ref "U2") (pin "4") (pinfunction "V-_4") (pintype "power_in"))
      (node (ref "U3") (pin "11") (pinfunction "V-_11") (pintype "power_in"))
      (node (ref "U4") (pin "11") (pinfunction "V-_11") (pintype "power_in"))
      (node (ref "U5") (pin "4") (pinfunction "V-_4") (pintype "power_in"))
    )
    (net (code "110") (name "unconnected-(1.4K-SWITCH-PadP$2_SWITCH)") (class "Default")
      (node (ref "1.4K") (pin "P$2_SWITCH") (pinfunction "SWITCH_P$2_SWITCH") (pintype "passive"))
    )
    (net (code "111") (name "unconnected-(1K-SWITCH-PadP$2_SWITCH)") (class "Default")
      (node (ref "1K") (pin "P$2_SWITCH") (pinfunction "SWITCH_P$2_SWITCH") (pintype "passive"))
    )
    (net (code "112") (name "unconnected-(2K-SWITCH-PadP$2_SWITCH)") (class "Default")
      (node (ref "2K") (pin "P$2_SWITCH") (pinfunction "SWITCH_P$2_SWITCH") (pintype "passive"))
    )
    (net (code "113") (name "unconnected-(3.5K-SWITCH-PadP$2_SWITCH)") (class "Default")
      (node (ref "3.5K") (pin "P$2_SWITCH") (pinfunction "SWITCH_P$2_SWITCH") (pintype "passive"))
    )
    (net (code "114") (name "unconnected-(200-SWITCH-PadP$2_SWITCH)") (class "Default")
      (node (ref "200") (pin "P$2_SWITCH") (pinfunction "SWITCH_P$2_SWITCH") (pintype "passive"))
    )
    (net (code "115") (name "unconnected-(350-SWITCH-PadP$2_SWITCH)") (class "Default")
      (node (ref "350") (pin "P$2_SWITCH") (pinfunction "SWITCH_P$2_SWITCH") (pintype "passive"))
    )
    (net (code "116") (name "unconnected-(500-SWITCH-PadP$2_SWITCH)") (class "Default")
      (node (ref "500") (pin "P$2_SWITCH") (pinfunction "SWITCH_P$2_SWITCH") (pintype "passive"))
    )
    (net (code "117") (name "unconnected-(700-SWITCH-PadP$2_SWITCH)") (class "Default")
      (node (ref "700") (pin "P$2_SWITCH") (pinfunction "SWITCH_P$2_SWITCH") (pintype "passive"))
    )
    (net (code "118") (name "unconnected-(<100-SWITCH-PadP$2_SWITCH)") (class "Default")
      (node (ref "<100") (pin "P$2_SWITCH") (pinfunction "SWITCH_P$2_SWITCH") (pintype "passive"))
    )
    (net (code "119") (name "unconnected-(>7K-SWITCH-PadP$2_SWITCH)") (class "Default")
      (node (ref ">7K") (pin "P$2_SWITCH") (pinfunction "SWITCH_P$2_SWITCH") (pintype "passive"))
    )
    (net (code "120") (name "unconnected-(SUM_OUT-SWITCH-PadP$2_SWITCH)") (class "Default")
      (node (ref "SUM_OUT") (pin "P$2_SWITCH") (pinfunction "SWITCH_P$2_SWITCH") (pintype "passive"))
    )
    (net (code "121") (name "unconnected-(VR1-PadA)") (class "Default")
      (node (ref "VR1") (pin "A") (pinfunction "A_A") (pintype "passive"))
    )
    (net (code "122") (name "unconnected-(VR3-PadA)") (class "Default")
      (node (ref "VR3") (pin "A") (pinfunction "A_A") (pintype "passive"))
    )
    (net (code "123") (name "unconnected-(VR5-PadA)") (class "Default")
      (node (ref "VR5") (pin "A") (pinfunction "A_A") (pintype "passive"))
    )
    (net (code "124") (name "unconnected-(VR7-PadA)") (class "Default")
      (node (ref "VR7") (pin "A") (pinfunction "A_A") (pintype "passive"))
    )
    (net (code "125") (name "unconnected-(VR9-PadA)") (class "Default")
      (node (ref "VR9") (pin "A") (pinfunction "A_A") (pintype "passive"))
    )
    (net (code "126") (name "unconnected-(VR11-PadA)") (class "Default")
      (node (ref "VR11") (pin "A") (pinfunction "A_A") (pintype "passive"))
    )
    (net (code "127") (name "unconnected-(VR13-PadA)") (class "Default")
      (node (ref "VR13") (pin "A") (pinfunction "A_A") (pintype "passive"))
    )
    (net (code "128") (name "unconnected-(VR15-PadA)") (class "Default")
      (node (ref "VR15") (pin "A") (pinfunction "A_A") (pintype "passive"))
    )
  )
)
